# Callisto_MSO_Teknic.net
KiCad netlist of a schematic drawn in EAGLE
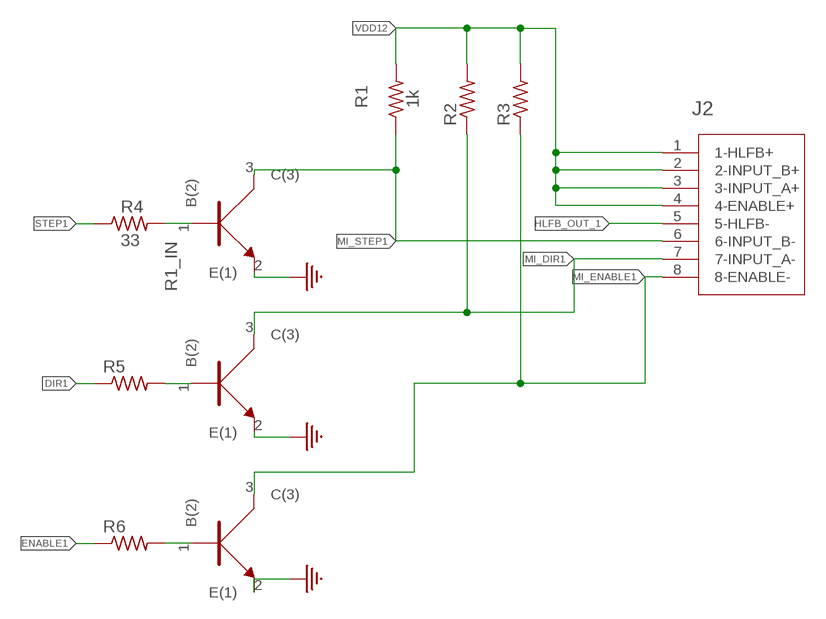
[diagram p0: schematic, sheet 1]

(export (version "E")
  (design (tool "Eeschema 10.0.6"))
  (components
    (comp (ref "J2")
      (value "TEKNIC_8PIN_MOTOR")
      (footprint "eagle-import:CON_39281083")
      (fields
        (field (name "MANUFACTURER_PART_NUMBER") "39281083")
        (field (name "COPYRIGHT") "Copyright (C) 2022 Ultra Librarian. All rights reserved.")
      )
      (libsource (lib "eagle-import") (part "TEKNIC_8PIN_MOTOR"))
    )
    (comp (ref "R1")
      (value "1k")
      (footprint "eagle-import:0805")
      (libsource (lib "eagle-import") (part "R_0805"))
    )
    (comp (ref "R2")
      (value "R_0805")
      (footprint "eagle-import:0805")
      (libsource (lib "eagle-import") (part "R_0805"))
    )
    (comp (ref "R3")
      (value "R_0805")
      (footprint "eagle-import:0805")
      (libsource (lib "eagle-import") (part "R_0805"))
    )
    (comp (ref "R4")
      (value "33")
      (footprint "eagle-import:0805")
      (libsource (lib "eagle-import") (part "R_0805"))
    )
    (comp (ref "R5")
      (value "R_0805")
      (footprint "eagle-import:0805")
      (libsource (lib "eagle-import") (part "R_0805"))
    )
    (comp (ref "R6")
      (value "R_0805")
      (footprint "eagle-import:0805")
      (libsource (lib "eagle-import") (part "R_0805"))
    )
    (comp (ref "U1")
      (value "NPN")
      (footprint "eagle-import:SOT323")
      (fields (field (name "PARTNO") "BC846BW_NPN"))
      (libsource (lib "eagle-import") (part "BC846BW"))
    )
    (comp (ref "U2")
      (value "NPN")
      (footprint "eagle-import:SOT323")
      (fields (field (name "PARTNO") "BC846BW_NPN"))
      (libsource (lib "eagle-import") (part "BC846BW"))
    )
    (comp (ref "U3")
      (value "NPN")
      (footprint "eagle-import:SOT323")
      (fields (field (name "PARTNO") "BC846BW_NPN"))
      (libsource (lib "eagle-import") (part "BC846BW"))
    )
  )
  (nets
    (net (code "1") (name "/R1_IN") (class "Default")
      (node (ref "R4") (pin "2") (pinfunction "2_2") (pintype "passive"))
      (node (ref "U1") (pin "1") (pinfunction "B(2)_1") (pintype "input"))
    )
    (net (code "2") (name "DIR1") (class "Default")
      (node (ref "R5") (pin "1") (pinfunction "1_1") (pintype "passive"))
    )
    (net (code "3") (name "ENABLE1") (class "Default")
      (node (ref "R6") (pin "1") (pinfunction "1_1") (pintype "passive"))
    )
    (net (code "4") (name "GND") (class "Default")
      (node (ref "U1") (pin "2") (pinfunction "E(1)_2") (pintype "output"))
      (node (ref "U2") (pin "2") (pinfunction "E(1)_2") (pintype "output"))
      (node (ref "U3") (pin "2") (pinfunction "E(1)_2") (pintype "output"))
    )
    (net (code "5") (name "HLFB_OUT_1") (class "Default")
      (node (ref "J2") (pin "5") (pinfunction "5-HLFB-_5") (pintype "passive"))
    )
    (net (code "6") (name "MI_DIR1") (class "Default")
      (node (ref "J2") (pin "7") (pinfunction "7-INPUT_A-_7") (pintype "passive"))
      (node (ref "R2") (pin "1") (pinfunction "1_1") (pintype "passive"))
      (node (ref "U2") (pin "3") (pinfunction "C(3)_3") (pintype "input"))
    )
    (net (code "7") (name "MI_ENABLE1") (class "Default")
      (node (ref "J2") (pin "8") (pinfunction "8-ENABLE-_8") (pintype "passive"))
      (node (ref "R3") (pin "1") (pinfunction "1_1") (pintype "passive"))
      (node (ref "U3") (pin "3") (pinfunction "C(3)_3") (pintype "input"))
    )
    (net (code "8") (name "MI_STEP1") (class "Default")
      (node (ref "J2") (pin "6") (pinfunction "6-INPUT_B-_6") (pintype "passive"))
      (node (ref "R1") (pin "1") (pinfunction "1_1") (pintype "passive"))
      (node (ref "U1") (pin "3") (pinfunction "C(3)_3") (pintype "input"))
    )
    (net (code "9") (name "Net-(U2-B(2))") (class "Default")
      (node (ref "R5") (pin "2") (pinfunction "2_2") (pintype "passive"))
      (node (ref "U2") (pin "1") (pinfunction "B(2)_1") (pintype "input"))
    )
    (net (code "10") (name "Net-(U3-B(2))") (class "Default")
      (node (ref "R6") (pin "2") (pinfunction "2_2") (pintype "passive"))
      (node (ref "U3") (pin "1") (pinfunction "B(2)_1") (pintype "input"))
    )
    (net (code "11") (name "STEP1") (class "Default")
      (node (ref "R4") (pin "1") (pinfunction "1_1") (pintype "passive"))
    )
    (net (code "12") (name "VDD12") (class "Default")
      (node (ref "J2") (pin "1") (pinfunction "1-HLFB+_1") (pintype "passive"))
      (node (ref "J2") (pin "2") (pinfunction "2-INPUT_B+_2") (pintype "passive"))
      (node (ref "J2") (pin "3") (pinfunction "3-INPUT_A+_3") (pintype "passive"))
      (node (ref "J2") (pin "4") (pinfunction "4-ENABLE+_4") (pintype "passive"))
      (node (ref "R1") (pin "2") (pinfunction "2_2") (pintype "passive"))
      (node (ref "R2") (pin "2") (pinfunction "2_2") (pintype "passive"))
      (node (ref "R3") (pin "2") (pinfunction "2_2") (pintype "passive"))
    )
  )
)
